# NodeSTM32.net
KiCad netlist of a schematic drawn in Altium Designer
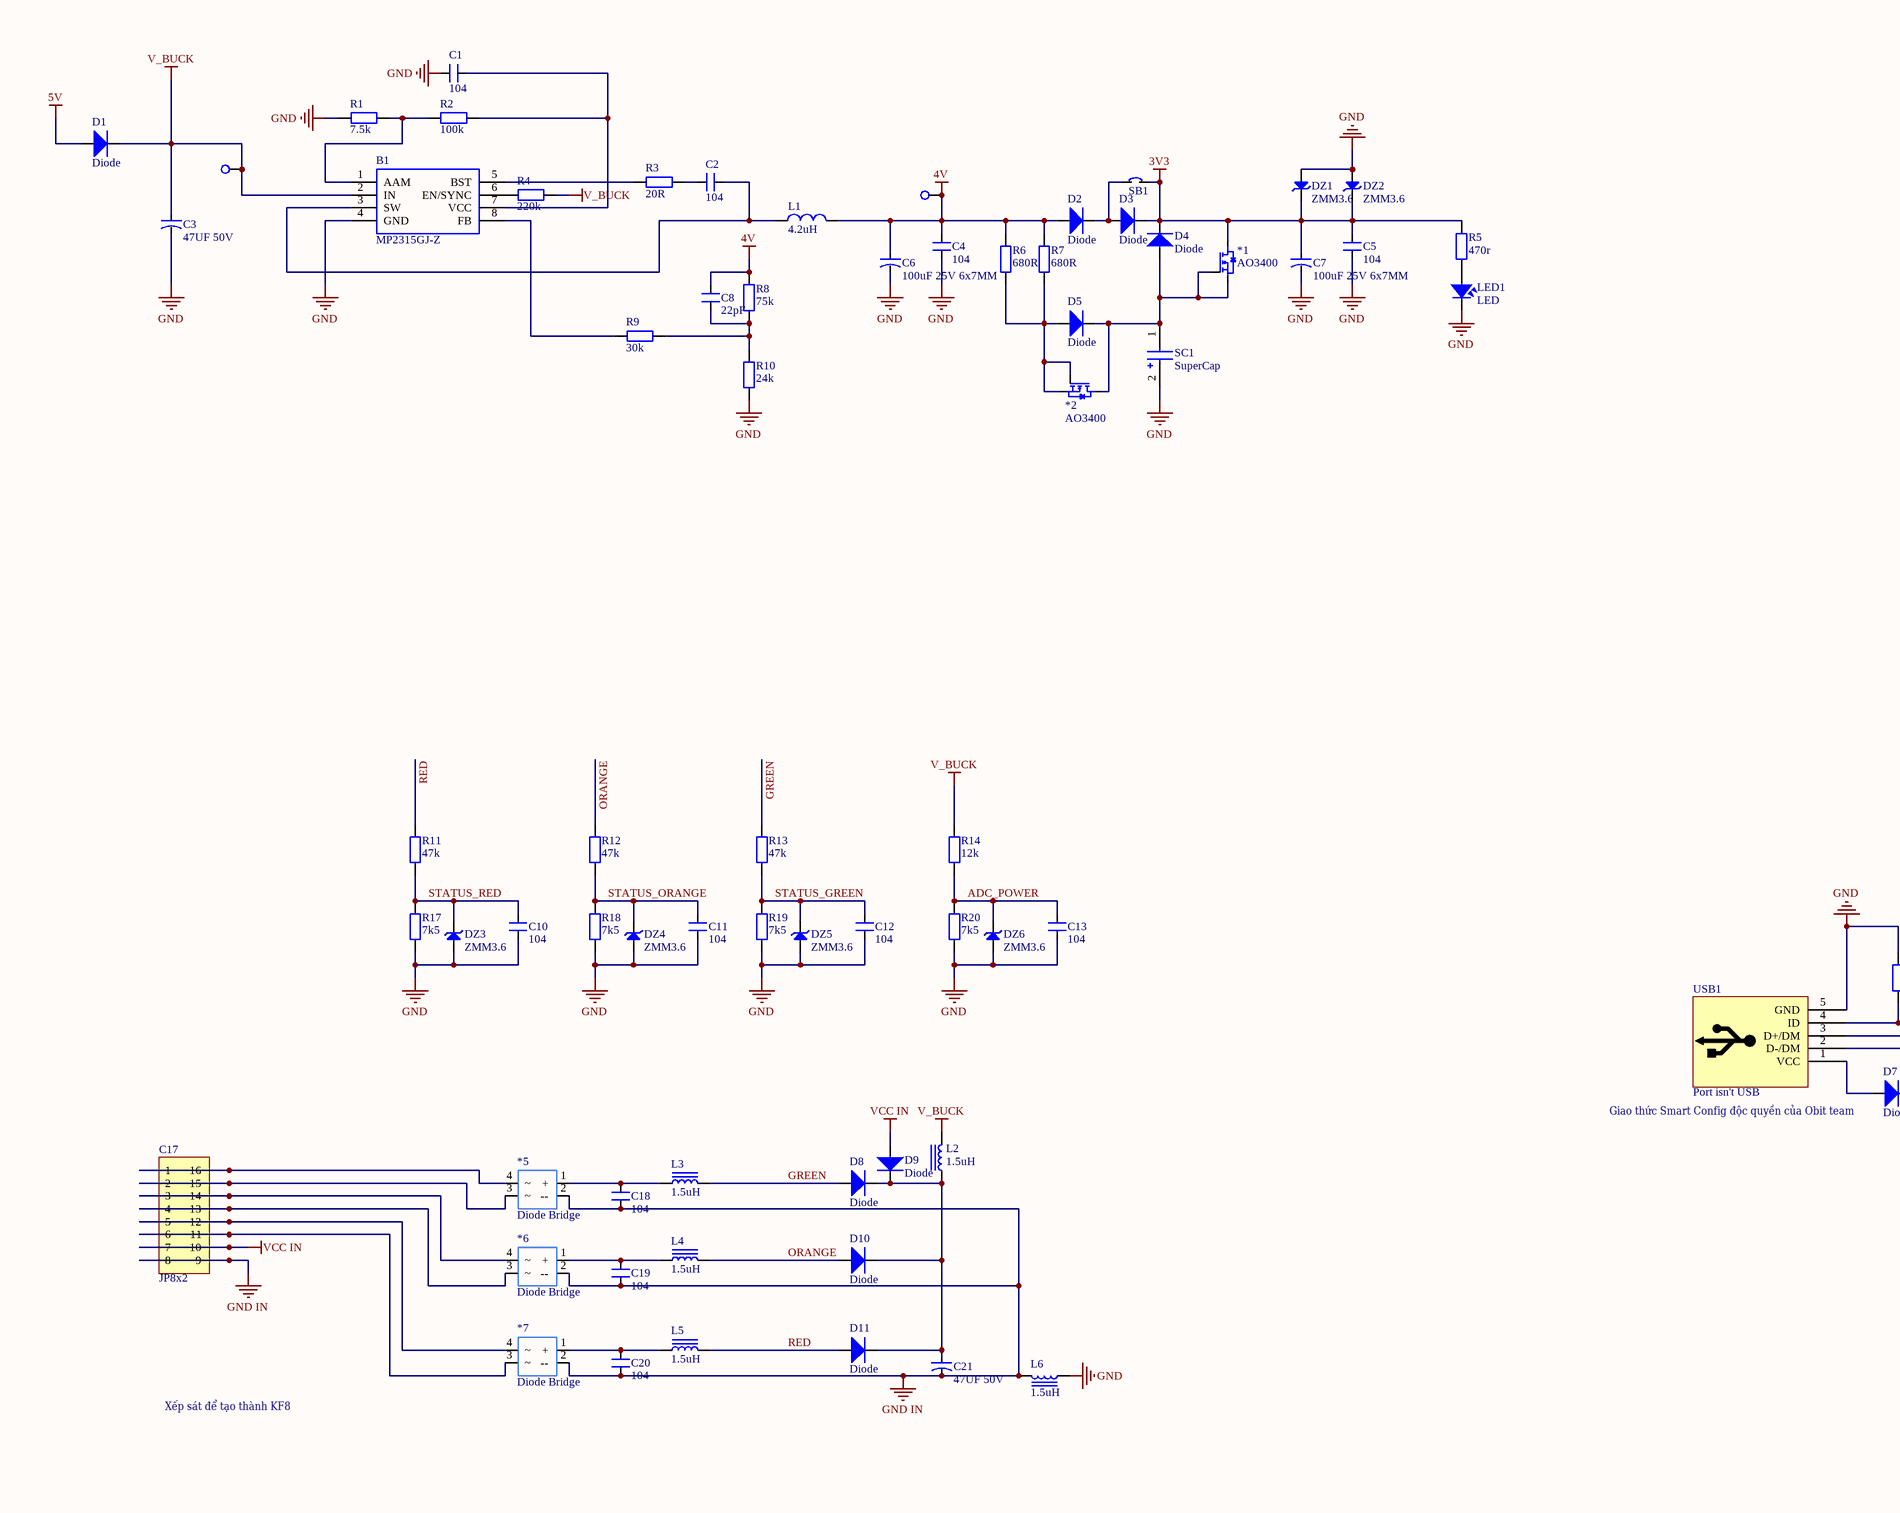
[diagram p0: NodeSTM32.SchDoc, left]
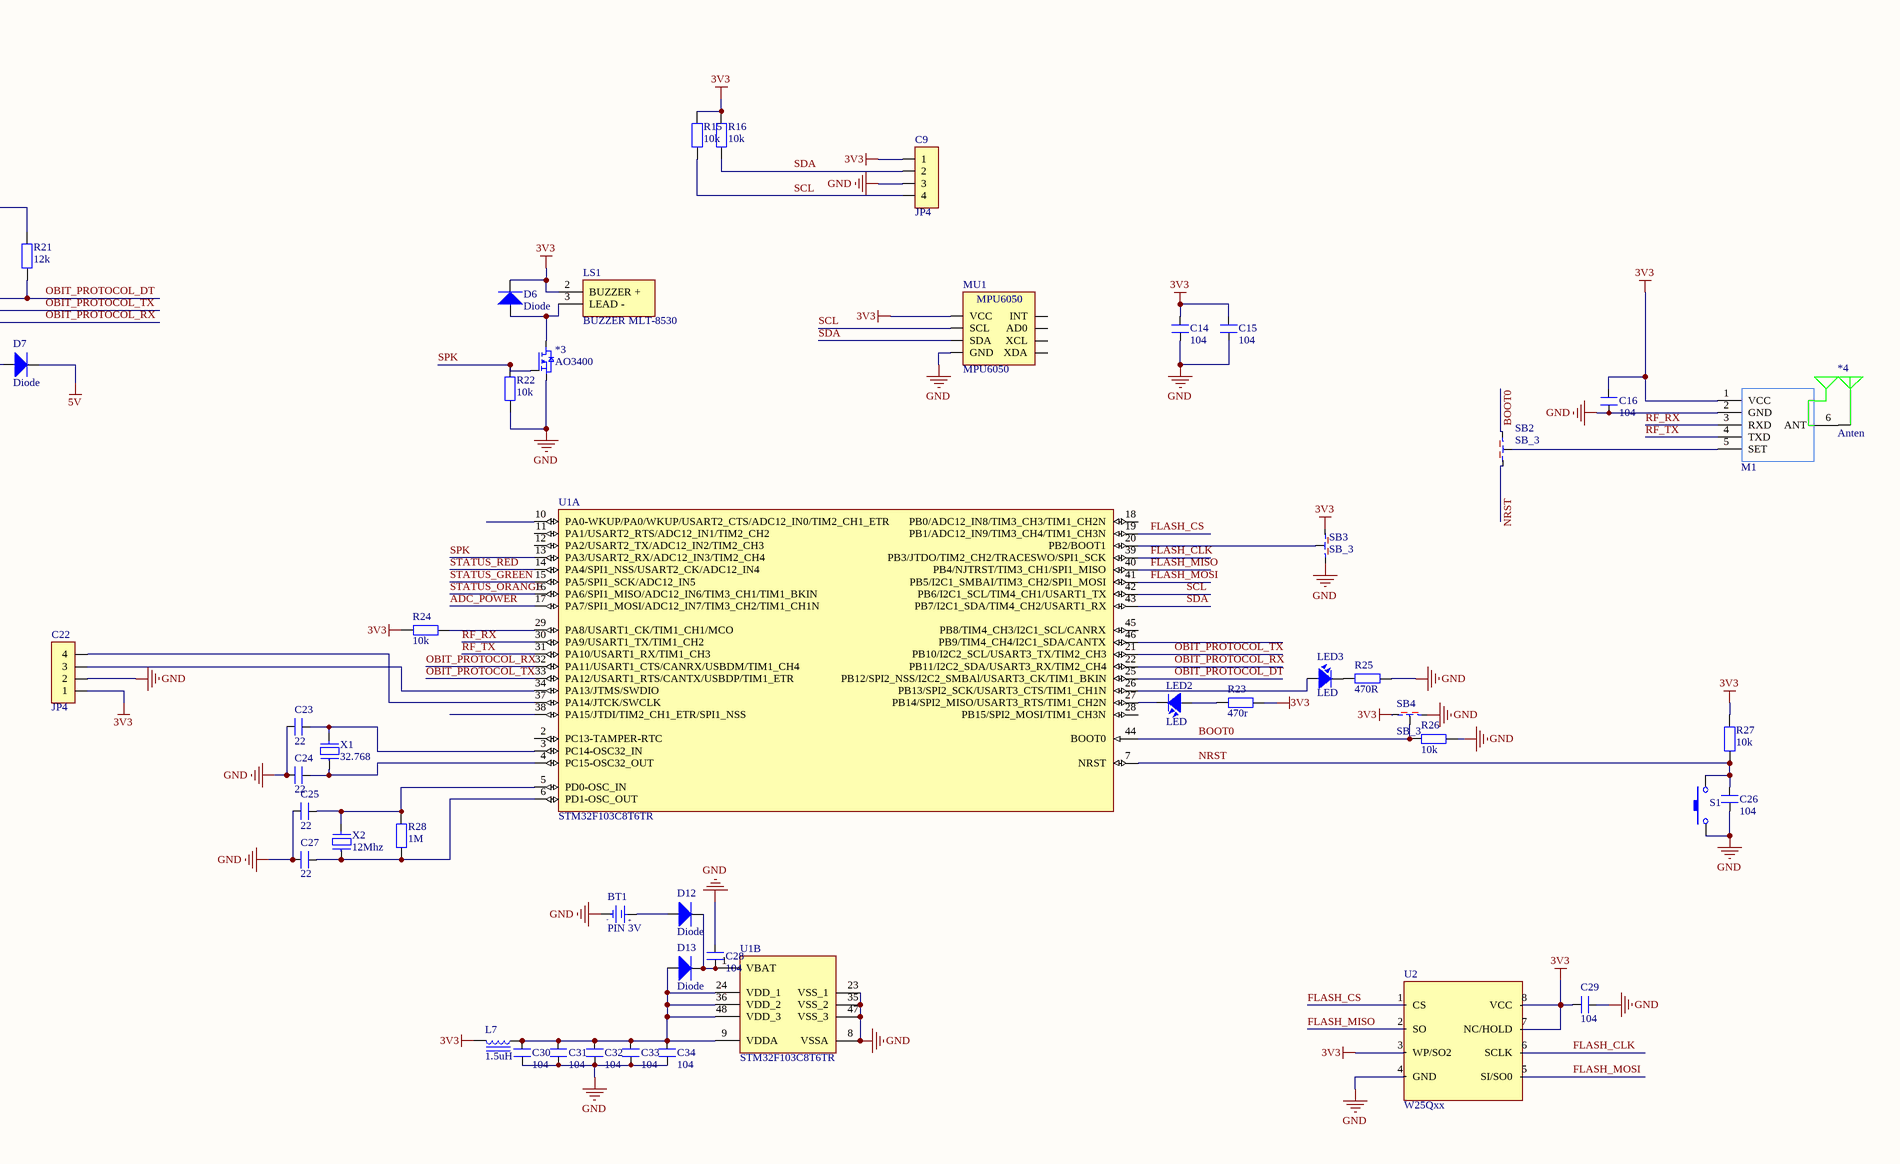
[diagram p1: NodeSTM32.SchDoc, right]

(export (version "E")
  (design (tool "Eeschema 10.0.6"))
  (components
    (comp (ref "*1") (value "AO3400") (footprint "SOT23-123") (libsource (lib "OBIT_TESLA") (part "AO3400")))
    (comp (ref "*2") (value "AO3400") (footprint "SOT23-123") (libsource (lib "OBIT_TESLA") (part "AO3400")))
    (comp (ref "*3") (value "AO3400") (footprint "SOT23-123") (libsource (lib "OBIT_TESLA") (part "AO3400")))
    (comp (ref "*4")
      (value "Anten")
      (footprint "LOXO_433_NGANG")
      (libsource (lib "OBIT_TESLA") (part "Anten"))
    )
    (comp (ref "*5")
      (value "Diode Bridge")
      (footprint "Diode Bridge 1A")
      (libsource (lib "OBIT_TESLA") (part "Diode Bridge"))
    )
    (comp (ref "*6")
      (value "Diode Bridge")
      (footprint "Diode Bridge 1A")
      (libsource (lib "OBIT_TESLA") (part "Diode Bridge"))
    )
    (comp (ref "*7")
      (value "Diode Bridge")
      (footprint "Diode Bridge 1A")
      (libsource (lib "OBIT_TESLA") (part "Diode Bridge"))
    )
    (comp (ref "*TP1") (value "TP") (footprint "TP") (libsource (lib "OBIT_TESLA") (part "TP")))
    (comp (ref "*TP2") (value "TP") (footprint "TP") (libsource (lib "OBIT_TESLA") (part "TP")))
    (comp (ref "B1")
      (value "MP2315GJ-Z")
      (footprint "SOT65P280X100-8N")
      (description "Switching Voltage Regulators 3A 24V 500kHz Sync buck")
      (libsource (lib "OBIT_TESLA") (part "MP2315GJ-Z"))
    )
    (comp (ref "BT1")
      (value "PIN 3V")
      (footprint "PIN CR1220-SMD")
      (description "Battery 3VDC")
      (libsource (lib "OBIT_TESLA") (part "PIN 3V"))
    )
    (comp (ref "C1")
      (value "104")
      (footprint "SM-0805")
      (description "Cap SMD")
      (libsource (lib "OBIT_TESLA") (part "CM"))
    )
    (comp (ref "C2")
      (value "104")
      (footprint "SM-0805")
      (description "Cap SMD")
      (libsource (lib "OBIT_TESLA") (part "CM"))
    )
    (comp (ref "C3")
      (value "47UF 50V")
      (footprint "CAP-ALU-SMD-6.3x7.7x2.2")
      (description "Tụ Nhôm 47UF 50V 6.3x5.5MM")
      (libsource (lib "Tesla_Thinh") (part "CN-ALU-SMD"))
    )
    (comp (ref "C4")
      (value "104")
      (footprint "SM-0805")
      (description "Cap SMD")
      (libsource (lib "OBIT_TESLA") (part "CM"))
    )
    (comp (ref "C5")
      (value "104")
      (footprint "SM-0805")
      (description "Cap SMD")
      (libsource (lib "OBIT_TESLA") (part "CM"))
    )
    (comp (ref "C6")
      (value "100uF 25V 6x7MM")
      (footprint "CAP-ALU-SMD-6.3x7.7x2.2")
      (description "Polarized Capacitor (Axial)")
      (libsource (lib "Tesla_Thinh") (part "CN-ALU-SMD"))
    )
    (comp (ref "C7")
      (value "100uF 25V 6x7MM")
      (footprint "CAP-ALU-SMD-6.3x7.7x2.2")
      (description "Polarized Capacitor (Axial)")
      (libsource (lib "Tesla_Thinh") (part "CN-ALU-SMD"))
    )
    (comp (ref "C8")
      (value "22pF")
      (footprint "SM-0805")
      (description "Cap SMD")
      (libsource (lib "OBIT_TESLA") (part "CM"))
    )
    (comp (ref "C9")
      (value "JP4")
      (footprint "JP4-C1T")
      (description "WR-PHD 2.54 mm Angled Socket Header")
      (fields
        (field (name "MANUFACTURER") "Würth Elektronik eiSos GmbH")
        (field (name "PARTNO") "613004143121")
      )
      (libsource (lib "OBIT_TESLA") (part "JP4"))
    )
    (comp (ref "C10")
      (value "104")
      (footprint "SM-0805")
      (description "Cap SMD")
      (libsource (lib "OBIT_TESLA") (part "CM"))
    )
    (comp (ref "C11")
      (value "104")
      (footprint "SM-0805")
      (description "Cap SMD")
      (libsource (lib "OBIT_TESLA") (part "CM"))
    )
    (comp (ref "C12")
      (value "104")
      (footprint "SM-0805")
      (description "Cap SMD")
      (libsource (lib "OBIT_TESLA") (part "CM"))
    )
    (comp (ref "C13")
      (value "104")
      (footprint "SM-0805")
      (description "Cap SMD")
      (libsource (lib "OBIT_TESLA") (part "CM"))
    )
    (comp (ref "C14")
      (value "104")
      (footprint "SM-0805")
      (description "Cap SMD")
      (libsource (lib "OBIT_TESLA") (part "CM"))
    )
    (comp (ref "C15")
      (value "104")
      (footprint "SM-0805")
      (description "Cap SMD")
      (libsource (lib "OBIT_TESLA") (part "CM"))
    )
    (comp (ref "C16")
      (value "104")
      (footprint "SM-0805")
      (description "Cap SMD")
      (libsource (lib "OBIT_TESLA") (part "CM"))
    )
    (comp (ref "C17")
      (value "JP8x2")
      (footprint "JP8-D2T")
      (description "WR-PHD 2.54 mm Dual Socket Header")
      (fields
        (field (name "MANUFACTURER") "Würth Elektronik eiSos GmbH")
        (field (name "PARTNO") "61301621821")
      )
      (libsource (lib "OBIT_TESLA") (part "JP8x2"))
    )
    (comp (ref "C18")
      (value "104")
      (footprint "SM-0805")
      (description "Cap SMD")
      (libsource (lib "OBIT_TESLA") (part "CM"))
    )
    (comp (ref "C19")
      (value "104")
      (footprint "SM-0805")
      (description "Cap SMD")
      (libsource (lib "OBIT_TESLA") (part "CM"))
    )
    (comp (ref "C20")
      (value "104")
      (footprint "SM-0805")
      (description "Cap SMD")
      (libsource (lib "OBIT_TESLA") (part "CM"))
    )
    (comp (ref "C21")
      (value "47UF 50V")
      (footprint "CAP-ALU-SMD-6.3x7.7x2.2")
      (description "Tụ Nhôm 47UF 50V 6.3x5.5MM")
      (libsource (lib "Tesla_Thinh") (part "CN-ALU-SMD"))
    )
    (comp (ref "C22")
      (value "JP4")
      (footprint "JP4-C1T")
      (description "WR-PHD 2.54 mm Angled Socket Header")
      (fields
        (field (name "MANUFACTURER") "Würth Elektronik eiSos GmbH")
        (field (name "PARTNO") "613004143121")
      )
      (libsource (lib "") (part "JP4_1"))
    )
    (comp (ref "C23")
      (value "22")
      (footprint "SM-0805")
      (description "Cap SMD")
      (libsource (lib "OBIT_TESLA") (part "CM"))
    )
    (comp (ref "C24")
      (value "22")
      (footprint "SM-0805")
      (description "Cap SMD")
      (libsource (lib "OBIT_TESLA") (part "CM"))
    )
    (comp (ref "C25")
      (value "22")
      (footprint "SM-0805")
      (description "Cap SMD")
      (libsource (lib "OBIT_TESLA") (part "CM"))
    )
    (comp (ref "C26")
      (value "104")
      (footprint "SM-0805")
      (description "Cap SMD")
      (libsource (lib "OBIT_TESLA") (part "CM"))
    )
    (comp (ref "C27")
      (value "22")
      (footprint "SM-0805")
      (description "Cap SMD")
      (libsource (lib "OBIT_TESLA") (part "CM"))
    )
    (comp (ref "C28")
      (value "104")
      (footprint "SM-0805")
      (description "Cap SMD")
      (libsource (lib "OBIT_TESLA") (part "CM"))
    )
    (comp (ref "C29")
      (value "104")
      (footprint "SM-0805")
      (description "Cap SMD")
      (libsource (lib "OBIT_TESLA") (part "CM"))
    )
    (comp (ref "C30")
      (value "104")
      (footprint "SM-0805")
      (description "Cap SMD")
      (libsource (lib "OBIT_TESLA") (part "CM"))
    )
    (comp (ref "C31")
      (value "104")
      (footprint "SM-0805")
      (description "Cap SMD")
      (libsource (lib "OBIT_TESLA") (part "CM"))
    )
    (comp (ref "C32")
      (value "104")
      (footprint "SM-0805")
      (description "Cap SMD")
      (libsource (lib "OBIT_TESLA") (part "CM"))
    )
    (comp (ref "C33")
      (value "104")
      (footprint "SM-0805")
      (description "Cap SMD")
      (libsource (lib "OBIT_TESLA") (part "CM"))
    )
    (comp (ref "C34")
      (value "104")
      (footprint "SM-0805")
      (description "Cap SMD")
      (libsource (lib "OBIT_TESLA") (part "CM"))
    )
    (comp (ref "D1") (value "Diode") (footprint "SOD123") (libsource (lib "OBIT_TESLA") (part "Diode")))
    (comp (ref "D2") (value "Diode") (footprint "DIO-SMD-123") (libsource (lib "OBIT_TESLA") (part "Diode")))
    (comp (ref "D3") (value "Diode") (footprint "DIO-SMD-123") (libsource (lib "OBIT_TESLA") (part "Diode")))
    (comp (ref "D4") (value "Diode") (footprint "DIO-SMD-123") (libsource (lib "OBIT_TESLA") (part "Diode")))
    (comp (ref "D5") (value "Diode") (footprint "DIO-SMD-123") (libsource (lib "OBIT_TESLA") (part "Diode")))
    (comp (ref "D6") (value "Diode") (footprint "DIO-SMD-123") (libsource (lib "OBIT_TESLA") (part "Diode")))
    (comp (ref "D7") (value "Diode") (footprint "DIO-SMD-123") (libsource (lib "OBIT_TESLA") (part "Diode")))
    (comp (ref "D8") (value "Diode") (footprint "DIO-SMD-123") (libsource (lib "OBIT_TESLA") (part "Diode")))
    (comp (ref "D9") (value "Diode") (footprint "DIO-SMD-123") (libsource (lib "OBIT_TESLA") (part "Diode")))
    (comp (ref "D10") (value "Diode") (footprint "DIO-SMD-123") (libsource (lib "OBIT_TESLA") (part "Diode")))
    (comp (ref "D11") (value "Diode") (footprint "DIO-SMD-123") (libsource (lib "OBIT_TESLA") (part "Diode")))
    (comp (ref "D12") (value "Diode") (footprint "SOD123") (libsource (lib "OBIT_TESLA") (part "Diode")))
    (comp (ref "D13") (value "Diode") (footprint "SOD123") (libsource (lib "OBIT_TESLA") (part "Diode")))
    (comp (ref "DZ1")
      (value "ZMM3.6")
      (footprint "SOD123")
      (description "DIODE GEN PURP 75V 200MA LLDS")
      (libsource (lib "Library") (part "DIODE Zener"))
    )
    (comp (ref "DZ2")
      (value "ZMM3.6")
      (footprint "DIO-SMD-123")
      (description "DIODE GEN PURP 75V 200MA LLDS")
      (libsource (lib "Library") (part "DIODE Zener"))
    )
    (comp (ref "DZ3")
      (value "ZMM3.6")
      (footprint "SOD123")
      (description "DIODE GEN PURP 75V 200MA LLDS")
      (libsource (lib "Library") (part "DIODE Zener"))
    )
    (comp (ref "DZ4")
      (value "ZMM3.6")
      (footprint "SOD123")
      (description "DIODE GEN PURP 75V 200MA LLDS")
      (libsource (lib "Library") (part "DIODE Zener"))
    )
    (comp (ref "DZ5")
      (value "ZMM3.6")
      (footprint "SOD123")
      (description "DIODE GEN PURP 75V 200MA LLDS")
      (libsource (lib "Library") (part "DIODE Zener"))
    )
    (comp (ref "DZ6")
      (value "ZMM3.6")
      (footprint "SOD123")
      (description "DIODE GEN PURP 75V 200MA LLDS")
      (libsource (lib "Library") (part "DIODE Zener"))
    )
    (comp (ref "L1")
      (value "4.2uH")
      (footprint "IND 4532-2P")
      (libsource (lib "AltiumLibraryTieuBao (1)") (part "INDUCTOR B"))
    )
    (comp (ref "L2")
      (value "1.5uH")
      (footprint "FER 0805/2012")
      (description "SMT Inductor")
      (libsource (lib "OBIT_TESLA") (part "Inductor"))
    )
    (comp (ref "L3")
      (value "1.5uH")
      (footprint "FER 0805/2012")
      (description "SMT Inductor")
      (libsource (lib "OBIT_TESLA") (part "Inductor"))
    )
    (comp (ref "L4")
      (value "1.5uH")
      (footprint "FER 0805/2012")
      (description "SMT Inductor")
      (libsource (lib "OBIT_TESLA") (part "Inductor"))
    )
    (comp (ref "L5")
      (value "1.5uH")
      (footprint "FER 0805/2012")
      (description "SMT Inductor")
      (libsource (lib "OBIT_TESLA") (part "Inductor"))
    )
    (comp (ref "L6")
      (value "1.5uH")
      (footprint "FER 0805/2012")
      (description "SMT Inductor")
      (libsource (lib "OBIT_TESLA") (part "Inductor"))
    )
    (comp (ref "L7")
      (value "1.5uH")
      (footprint "FER 0805/2012")
      (description "SMT Inductor")
      (libsource (lib "OBIT_TESLA") (part "Inductor"))
    )
    (comp (ref "LED1")
      (value "LED")
      (footprint "SM-LED-0805-Blue")
      (libsource (lib "OBIT_TESLA") (part "LED"))
    )
    (comp (ref "LED2")
      (value "LED")
      (footprint "SM-LED-0805-Blue")
      (libsource (lib "OBIT_TESLA") (part "LED"))
    )
    (comp (ref "LED3")
      (value "LED")
      (footprint "SM-LED-0805-Blue")
      (libsource (lib "OBIT_TESLA") (part "LED"))
    )
    (comp (ref "LS1")
      (value "BUZZER MLT-8530")
      (footprint "MLT8530")
      (description "Loudspeaker or Buzzer")
      (fields (field (name "MANUFACTURER_PART_NUMBER") "MLT-8530"))
      (libsource (lib "OBIT_TESLA") (part "BUZZER MLT-8530"))
    )
    (comp (ref "M1")
      (value "CC1101")
      (footprint "CC1101 UART HC11")
      (description "OBIT TEAM\r\nCC1101 UART 433MHZ")
      (libsource (lib "OBIT_TESLA") (part "CC1101 UART HC11"))
    )
    (comp (ref "MU1")
      (value "MPU6050")
      (footprint "MPU6050")
      (fields
        (field (name "MANUFACTURER") "Würth Elektronik eiSos GmbH")
        (field (name "PARTNO") "613004143121")
      )
      (libsource (lib "Tesla_Thinh") (part "MPU6050"))
    )
    (comp (ref "R1")
      (value "7.5k")
      (footprint "RES-SMD-0805")
      (description "Resistor R1/4W")
      (libsource (lib "OBIT_TESLA") (part "R"))
    )
    (comp (ref "R2")
      (value "100k")
      (footprint "RES-SMD-0805")
      (description "Resistor R1/4W")
      (libsource (lib "OBIT_TESLA") (part "R"))
    )
    (comp (ref "R3")
      (value "20R")
      (footprint "RES-SMD-0805")
      (description "Resistor R1/4W")
      (libsource (lib "OBIT_TESLA") (part "R"))
    )
    (comp (ref "R4")
      (value "220k")
      (footprint "RES-SMD-0805")
      (description "Resistor R1/4W")
      (libsource (lib "OBIT_TESLA") (part "R"))
    )
    (comp (ref "R5")
      (value "470r")
      (footprint "RES-SMD-0805")
      (description "Resistor R1/4W")
      (libsource (lib "OBIT_TESLA") (part "R"))
    )
    (comp (ref "R6")
      (value "680R")
      (footprint "RES-SMD-0805")
      (description "Resistor R1/4W")
      (libsource (lib "OBIT_TESLA") (part "R"))
    )
    (comp (ref "R7")
      (value "680R")
      (footprint "RES-SMD-0805")
      (description "Resistor R1/4W")
      (libsource (lib "OBIT_TESLA") (part "R"))
    )
    (comp (ref "R8")
      (value "75k")
      (footprint "RES-SMD-0805")
      (description "Resistor R1/4W")
      (libsource (lib "OBIT_TESLA") (part "R"))
    )
    (comp (ref "R9")
      (value "30k")
      (footprint "RES-SMD-0805")
      (description "Resistor R1/4W")
      (libsource (lib "OBIT_TESLA") (part "R"))
    )
    (comp (ref "R10")
      (value "24k")
      (footprint "RES-SMD-0805")
      (description "Resistor R1/4W")
      (libsource (lib "OBIT_TESLA") (part "R"))
    )
    (comp (ref "R11")
      (value "47k")
      (footprint "RES-SMD-0805")
      (description "Resistor R1/4W")
      (libsource (lib "OBIT_TESLA") (part "R"))
    )
    (comp (ref "R12")
      (value "47k")
      (footprint "RES-SMD-0805")
      (description "Resistor R1/4W")
      (libsource (lib "OBIT_TESLA") (part "R"))
    )
    (comp (ref "R13")
      (value "47k")
      (footprint "RES-SMD-0805")
      (description "Resistor R1/4W")
      (libsource (lib "OBIT_TESLA") (part "R"))
    )
    (comp (ref "R14")
      (value "12k")
      (footprint "RES-SMD-0805")
      (description "Resistor R1/4W")
      (libsource (lib "OBIT_TESLA") (part "R"))
    )
    (comp (ref "R15")
      (value "10k")
      (footprint "RES-SMD-0805")
      (description "Resistor R1/4W")
      (libsource (lib "OBIT_TESLA") (part "R"))
    )
    (comp (ref "R16")
      (value "10k")
      (footprint "RES-SMD-0805")
      (description "Resistor R1/4W")
      (libsource (lib "OBIT_TESLA") (part "R"))
    )
    (comp (ref "R17")
      (value "7k5")
      (footprint "RES-SMD-0805")
      (description "Resistor R1/4W")
      (libsource (lib "OBIT_TESLA") (part "R"))
    )
    (comp (ref "R18")
      (value "7k5")
      (footprint "RES-SMD-0805")
      (description "Resistor R1/4W")
      (libsource (lib "OBIT_TESLA") (part "R"))
    )
    (comp (ref "R19")
      (value "7k5")
      (footprint "RES-SMD-0805")
      (description "Resistor R1/4W")
      (libsource (lib "OBIT_TESLA") (part "R"))
    )
    (comp (ref "R20")
      (value "7k5")
      (footprint "RES-SMD-0805")
      (description "Resistor R1/4W")
      (libsource (lib "OBIT_TESLA") (part "R"))
    )
    (comp (ref "R21")
      (value "12k")
      (footprint "RES-SMD-0805")
      (description "Resistor R1/4W")
      (libsource (lib "OBIT_TESLA") (part "R"))
    )
    (comp (ref "R22")
      (value "10k")
      (footprint "RES-SMD-0805")
      (description "Resistor R1/4W")
      (libsource (lib "OBIT_TESLA") (part "R"))
    )
    (comp (ref "R23")
      (value "470r")
      (footprint "RES-SMD-0805")
      (description "Resistor R1/4W")
      (libsource (lib "OBIT_TESLA") (part "R"))
    )
    (comp (ref "R24")
      (value "10k")
      (footprint "RES-SMD-0805")
      (description "Resistor R1/4W")
      (libsource (lib "OBIT_TESLA") (part "R"))
    )
    (comp (ref "R25")
      (value "470R")
      (footprint "RES-SMD-0805")
      (description "Resistor R1/4W")
      (libsource (lib "OBIT_TESLA") (part "R"))
    )
    (comp (ref "R26")
      (value "10k")
      (footprint "RES-SMD-0805")
      (description "Resistor R1/4W")
      (libsource (lib "OBIT_TESLA") (part "R"))
    )
    (comp (ref "R27")
      (value "10k")
      (footprint "RES-SMD-0805")
      (description "Resistor R1/4W")
      (libsource (lib "OBIT_TESLA") (part "R"))
    )
    (comp (ref "R28")
      (value "1M")
      (footprint "RES-SMD-0805")
      (description "Resistor R1/4W")
      (libsource (lib "OBIT_TESLA") (part "R"))
    )
    (comp (ref "S1")
      (value "SW")
      (footprint "BUTTON-SMD 2PIN")
      (description "Switch-Button")
      (libsource (lib "OBIT_TESLA") (part "SW-Button"))
    )
    (comp (ref "SB1") (value "SB") (footprint "SB") (libsource (lib "OBIT_TESLA") (part "SB")))
    (comp (ref "SB2") (value "SB_3") (footprint "SB_3") (libsource (lib "OBIT_TESLA") (part "SB_3")))
    (comp (ref "SB3") (value "SB_3") (footprint "SB_3") (libsource (lib "OBIT_TESLA") (part "SB_3")))
    (comp (ref "SB4") (value "SB_3") (footprint "SB_3") (libsource (lib "OBIT_TESLA") (part "SB_3")))
    (comp (ref "SC1")
      (value "SuperCap")
      (footprint "SuperCapacitor")
      (libsource (lib "OBIT_TESLA") (part "5.5V 0.22F"))
    )
    (comp (ref "U1")
      (value "STM32F103C8T6TR")
      (footprint "STM-LQFP48_N")
      (libsource (lib "OBIT_TESLA") (part "STM32F103C8T6TR"))
    )
    (comp (ref "U2") (value "W25Qxx") (footprint "SO-8N") (libsource (lib "OBIT_TESLA") (part "W25Qxx")))
    (comp (ref "USB1")
      (value "Port isn't USB")
      (footprint "USB-M1")
      (libsource (lib "OBIT_TESLA") (part "USB_M"))
    )
    (comp (ref "X1")
      (value "32.768")
      (footprint "XT32k")
      (description "Crystal, 32.768 KHz, -40 to 85 degC, 3.2 x 1.5 x 0.9 mm SMD")
      (libsource (lib "OBIT_TESLA") (part "XT2"))
    )
    (comp (ref "X2")
      (value "12Mhz")
      (footprint "XT2")
      (description "Crystal, 32.768 KHz, -40 to 85 degC, 3.2 x 1.5 x 0.9 mm SMD")
      (libsource (lib "OBIT_TESLA") (part "XT2"))
    )
  )
  (nets
    (net (code "1") (name "/ADC_POWER") (class "Default")
      (node (ref "C13") (pin "2") (pinfunction "2_2") (pintype "passive"))
      (node (ref "DZ6") (pin "2") (pinfunction "K_2") (pintype "passive"))
      (node (ref "R14") (pin "2") (pinfunction "2_2") (pintype "passive"))
      (node (ref "R20") (pin "1") (pinfunction "1_1") (pintype "passive"))
      (node (ref "U1") (pin "17") (pinfunction "PA7/SPI1_MOSI/ADC12_IN7/TIM3_CH2/TIM1_CH1N_17") (pintype "bidirectional"))
    )
    (net (code "2") (name "/BOOT0") (class "Default")
      (node (ref "R26") (pin "2") (pinfunction "2_2") (pintype "passive"))
      (node (ref "SB2") (pin "3") (pinfunction "3_3") (pintype "passive"))
      (node (ref "SB4") (pin "2") (pinfunction "2_2") (pintype "passive"))
      (node (ref "U1") (pin "44") (pinfunction "BOOT0_44") (pintype "input"))
    )
    (net (code "3") (name "/FLASH_CLK") (class "Default")
      (node (ref "U1") (pin "39") (pinfunction "PB3/JTDO/TIM2_CH2/TRACESWO/SPI1_SCK_39") (pintype "bidirectional"))
      (node (ref "U2") (pin "6") (pinfunction "SCLK_6") (pintype "passive"))
    )
    (net (code "4") (name "/FLASH_CS") (class "Default")
      (node (ref "U1") (pin "19") (pinfunction "PB1/ADC12_IN9/TIM3_CH4/TIM1_CH3N_19") (pintype "bidirectional"))
      (node (ref "U2") (pin "1") (pinfunction "CS_1") (pintype "passive"))
    )
    (net (code "5") (name "/FLASH_MISO") (class "Default")
      (node (ref "U1") (pin "40") (pinfunction "PB4/NJTRST/TIM3_CH1/SPI1_MISO_40") (pintype "bidirectional"))
      (node (ref "U2") (pin "2") (pinfunction "SO_2") (pintype "passive"))
    )
    (net (code "6") (name "/FLASH_MOSI") (class "Default")
      (node (ref "U1") (pin "41") (pinfunction "PB5/I2C1_SMBAI/TIM3_CH2/SPI1_MOSI_41") (pintype "bidirectional"))
      (node (ref "U2") (pin "5") (pinfunction "SI/SO0_5") (pintype "passive"))
    )
    (net (code "7") (name "/GREEN") (class "Default")
      (node (ref "D8") (pin "1") (pinfunction "1_1") (pintype "passive"))
      (node (ref "L3") (pin "2") (pinfunction "2_2") (pintype "passive"))
      (node (ref "R13") (pin "1") (pinfunction "1_1") (pintype "passive"))
    )
    (net (code "8") (name "/NRST") (class "Default")
      (node (ref "C26") (pin "1") (pinfunction "1_1") (pintype "passive"))
      (node (ref "R27") (pin "1") (pinfunction "1_1") (pintype "passive"))
      (node (ref "S1") (pin "2") (pinfunction "2_2") (pintype "passive"))
      (node (ref "SB2") (pin "1") (pinfunction "1_1") (pintype "passive"))
      (node (ref "U1") (pin "7") (pinfunction "NRST_7") (pintype "bidirectional"))
    )
    (net (code "9") (name "/OBIT_PROTOCOL_DT") (class "Default")
      (node (ref "R21") (pin "2") (pinfunction "2_2") (pintype "passive"))
      (node (ref "U1") (pin "25") (pinfunction "PB12/SPI2_NSS/I2C2_SMBAl/USART3_CK/TIM1_BKIN_25") (pintype "bidirectional"))
      (node (ref "USB1") (pin "4") (pinfunction "ID_4") (pintype "passive"))
    )
    (net (code "10") (name "/OBIT_PROTOCOL_RX") (class "Default")
      (node (ref "U1") (pin "22") (pinfunction "PB11/I2C2_SDA/USART3_RX/TIM2_CH4_22") (pintype "bidirectional"))
      (node (ref "U1") (pin "32") (pinfunction "PA11/USART1_CTS/CANRX/USBDM/TIM1_CH4_32") (pintype "bidirectional"))
      (node (ref "USB1") (pin "2") (pinfunction "D-/DM_2") (pintype "passive"))
    )
    (net (code "11") (name "/OBIT_PROTOCOL_TX") (class "Default")
      (node (ref "U1") (pin "21") (pinfunction "PB10/I2C2_SCL/USART3_TX/TIM2_CH3_21") (pintype "bidirectional"))
      (node (ref "U1") (pin "33") (pinfunction "PA12/USART1_RTS/CANTX/USBDP/TIM1_ETR_33") (pintype "bidirectional"))
      (node (ref "USB1") (pin "3") (pinfunction "D+/DM_3") (pintype "passive"))
    )
    (net (code "12") (name "/ORANGE") (class "Default")
      (node (ref "D10") (pin "1") (pinfunction "1_1") (pintype "passive"))
      (node (ref "L4") (pin "2") (pinfunction "2_2") (pintype "passive"))
      (node (ref "R12") (pin "1") (pinfunction "1_1") (pintype "passive"))
    )
    (net (code "13") (name "/RED") (class "Default")
      (node (ref "D11") (pin "1") (pinfunction "1_1") (pintype "passive"))
      (node (ref "L5") (pin "2") (pinfunction "2_2") (pintype "passive"))
      (node (ref "R11") (pin "1") (pinfunction "1_1") (pintype "passive"))
    )
    (net (code "14") (name "/RF_RX") (class "Default")
      (node (ref "M1") (pin "3") (pinfunction "RXD_3") (pintype "passive"))
      (node (ref "U1") (pin "30") (pinfunction "PA9/USART1_TX/TIM1_CH2_30") (pintype "bidirectional"))
    )
    (net (code "15") (name "/RF_TX") (class "Default")
      (node (ref "M1") (pin "4") (pinfunction "TXD_4") (pintype "passive"))
      (node (ref "U1") (pin "31") (pinfunction "PA10/USART1_RX/TIM1_CH3_31") (pintype "bidirectional"))
    )
    (net (code "16") (name "/SCL") (class "Default")
      (node (ref "C9") (pin "4") (pinfunction "4_4") (pintype "passive"))
      (node (ref "MU1") (pin "3") (pinfunction "SCL_3") (pintype "passive"))
      (node (ref "R15") (pin "1") (pinfunction "1_1") (pintype "passive"))
      (node (ref "U1") (pin "42") (pinfunction "PB6/I2C1_SCL/TIM4_CH1/USART1_TX_42") (pintype "bidirectional"))
    )
    (net (code "17") (name "/SDA") (class "Default")
      (node (ref "C9") (pin "2") (pinfunction "2_2") (pintype "passive"))
      (node (ref "MU1") (pin "4") (pinfunction "SDA_4") (pintype "passive"))
      (node (ref "R16") (pin "1") (pinfunction "1_1") (pintype "passive"))
      (node (ref "U1") (pin "43") (pinfunction "PB7/I2C1_SDA/TIM4_CH2/USART1_RX_43") (pintype "bidirectional"))
    )
    (net (code "18") (name "/SPK") (class "Default")
      (node (ref "*3") (pin "1") (pintype "passive"))
      (node (ref "R22") (pin "1") (pinfunction "1_1") (pintype "passive"))
      (node (ref "U1") (pin "13") (pinfunction "PA3/USART2_RX/ADC12_IN3/TIM2_CH4_13") (pintype "bidirectional"))
    )
    (net (code "19") (name "/STATUS_GREEN") (class "Default")
      (node (ref "C12") (pin "2") (pinfunction "2_2") (pintype "passive"))
      (node (ref "DZ5") (pin "2") (pinfunction "K_2") (pintype "passive"))
      (node (ref "R13") (pin "2") (pinfunction "2_2") (pintype "passive"))
      (node (ref "R19") (pin "1") (pinfunction "1_1") (pintype "passive"))
      (node (ref "U1") (pin "15") (pinfunction "PA5/SPI1_SCK/ADC12_IN5_15") (pintype "bidirectional"))
    )
    (net (code "20") (name "/STATUS_ORANGE") (class "Default")
      (node (ref "C11") (pin "2") (pinfunction "2_2") (pintype "passive"))
      (node (ref "DZ4") (pin "2") (pinfunction "K_2") (pintype "passive"))
      (node (ref "R12") (pin "2") (pinfunction "2_2") (pintype "passive"))
      (node (ref "R18") (pin "1") (pinfunction "1_1") (pintype "passive"))
      (node (ref "U1") (pin "16") (pinfunction "PA6/SPI1_MISO/ADC12_IN6/TIM3_CH1/TIM1_BKIN_16") (pintype "bidirectional"))
    )
    (net (code "21") (name "/STATUS_RED") (class "Default")
      (node (ref "C10") (pin "2") (pinfunction "2_2") (pintype "passive"))
      (node (ref "DZ3") (pin "2") (pinfunction "K_2") (pintype "passive"))
      (node (ref "R11") (pin "2") (pinfunction "2_2") (pintype "passive"))
      (node (ref "R17") (pin "1") (pinfunction "1_1") (pintype "passive"))
      (node (ref "U1") (pin "14") (pinfunction "PA4/SPI1_NSS/USART2_CK/ADC12_IN4_14") (pintype "bidirectional"))
    )
    (net (code "22") (name "3V3") (class "Default")
      (node (ref "*1") (pin "2") (pintype "passive"))
      (node (ref "C14") (pin "2") (pinfunction "2_2") (pintype "passive"))
      (node (ref "C15") (pin "2") (pinfunction "2_2") (pintype "passive"))
      (node (ref "C16") (pin "2") (pinfunction "2_2") (pintype "passive"))
      (node (ref "C22") (pin "1") (pinfunction "1_1") (pintype "passive"))
      (node (ref "C29") (pin "1") (pinfunction "1_1") (pintype "passive"))
      (node (ref "C5") (pin "2") (pinfunction "2_2") (pintype "passive"))
      (node (ref "C7") (pin "1") (pinfunction "1_1") (pintype "passive"))
      (node (ref "C9") (pin "1") (pinfunction "1_1") (pintype "passive"))
      (node (ref "D3") (pin "2") (pinfunction "2_2") (pintype "passive"))
      (node (ref "D4") (pin "2") (pinfunction "2_2") (pintype "passive"))
      (node (ref "D6") (pin "2") (pinfunction "2_2") (pintype "passive"))
      (node (ref "DZ1") (pin "2") (pinfunction "K_2") (pintype "passive"))
      (node (ref "DZ2") (pin "2") (pinfunction "K_2") (pintype "passive"))
      (node (ref "L7") (pin "2") (pinfunction "2_2") (pintype "passive"))
      (node (ref "LS1") (pin "2") (pinfunction "BUZZER_+_2") (pintype "passive"))
      (node (ref "M1") (pin "1") (pinfunction "VCC_1") (pintype "passive"))
      (node (ref "MU1") (pin "1") (pinfunction "VCC_1") (pintype "passive"))
      (node (ref "R15") (pin "2") (pinfunction "2_2") (pintype "passive"))
      (node (ref "R16") (pin "2") (pinfunction "2_2") (pintype "passive"))
      (node (ref "R23") (pin "2") (pinfunction "2_2") (pintype "passive"))
      (node (ref "R24") (pin "2") (pinfunction "2_2") (pintype "passive"))
      (node (ref "R27") (pin "2") (pinfunction "2_2") (pintype "passive"))
      (node (ref "R5") (pin "2") (pinfunction "2_2") (pintype "passive"))
      (node (ref "SB1") (pin "2") (pintype "passive"))
      (node (ref "SB3") (pin "1") (pinfunction "1_1") (pintype "passive"))
      (node (ref "SB4") (pin "1") (pinfunction "1_1") (pintype "passive"))
      (node (ref "U2") (pin "3") (pinfunction "WP/SO2_3") (pintype "passive"))
      (node (ref "U2") (pin "7") (pinfunction "NC/HOLD_7") (pintype "passive"))
      (node (ref "U2") (pin "8") (pinfunction "VCC_8") (pintype "passive"))
    )
    (net (code "23") (name "4V") (class "Default")
      (node (ref "*TP2") (pin "1") (pintype "passive"))
      (node (ref "C4") (pin "2") (pinfunction "2_2") (pintype "passive"))
      (node (ref "C6") (pin "1") (pinfunction "1_1") (pintype "passive"))
      (node (ref "C8") (pin "2") (pinfunction "2_2") (pintype "passive"))
      (node (ref "D2") (pin "1") (pinfunction "1_1") (pintype "passive"))
      (node (ref "L1") (pin "2") (pinfunction "2_2") (pintype "passive"))
      (node (ref "R6") (pin "1") (pinfunction "1_1") (pintype "passive"))
      (node (ref "R7") (pin "1") (pinfunction "1_1") (pintype "passive"))
      (node (ref "R8") (pin "1") (pinfunction "1_1") (pintype "passive"))
    )
    (net (code "24") (name "5V") (class "Default")
      (node (ref "D1") (pin "1") (pinfunction "1_1") (pintype "passive"))
      (node (ref "D7") (pin "2") (pinfunction "2_2") (pintype "passive"))
    )
    (net (code "25") (name "GND") (class "Default")
      (node (ref "*3") (pin "3") (pintype "passive"))
      (node (ref "B1") (pin "4") (pinfunction "GND_4") (pintype "passive"))
      (node (ref "BT1") (pin "2") (pinfunction "GND_2") (pintype "passive"))
      (node (ref "C1") (pin "2") (pinfunction "2_2") (pintype "passive"))
      (node (ref "C10") (pin "1") (pinfunction "1_1") (pintype "passive"))
      (node (ref "C11") (pin "1") (pinfunction "1_1") (pintype "passive"))
      (node (ref "C12") (pin "1") (pinfunction "1_1") (pintype "passive"))
      (node (ref "C13") (pin "1") (pinfunction "1_1") (pintype "passive"))
      (node (ref "C14") (pin "1") (pinfunction "1_1") (pintype "passive"))
      (node (ref "C15") (pin "1") (pinfunction "1_1") (pintype "passive"))
      (node (ref "C16") (pin "1") (pinfunction "1_1") (pintype "passive"))
      (node (ref "C22") (pin "2") (pinfunction "2_2") (pintype "passive"))
      (node (ref "C23") (pin "2") (pinfunction "2_2") (pintype "passive"))
      (node (ref "C24") (pin "2") (pinfunction "2_2") (pintype "passive"))
      (node (ref "C25") (pin "2") (pinfunction "2_2") (pintype "passive"))
      (node (ref "C26") (pin "2") (pinfunction "2_2") (pintype "passive"))
      (node (ref "C27") (pin "2") (pinfunction "2_2") (pintype "passive"))
      (node (ref "C28") (pin "1") (pinfunction "1_1") (pintype "passive"))
      (node (ref "C29") (pin "2") (pinfunction "2_2") (pintype "passive"))
      (node (ref "C3") (pin "2") (pinfunction "2_2") (pintype "passive"))
      (node (ref "C30") (pin "2") (pinfunction "2_2") (pintype "passive"))
      (node (ref "C31") (pin "2") (pinfunction "2_2") (pintype "passive"))
      (node (ref "C32") (pin "2") (pinfunction "2_2") (pintype "passive"))
      (node (ref "C33") (pin "2") (pinfunction "2_2") (pintype "passive"))
      (node (ref "C34") (pin "2") (pinfunction "2_2") (pintype "passive"))
      (node (ref "C4") (pin "1") (pinfunction "1_1") (pintype "passive"))
      (node (ref "C5") (pin "1") (pinfunction "1_1") (pintype "passive"))
      (node (ref "C6") (pin "2") (pinfunction "2_2") (pintype "passive"))
      (node (ref "C7") (pin "2") (pinfunction "2_2") (pintype "passive"))
      (node (ref "C9") (pin "3") (pinfunction "3_3") (pintype "passive"))
      (node (ref "DZ1") (pin "1") (pinfunction "A_1") (pintype "passive"))
      (node (ref "DZ2") (pin "1") (pinfunction "A_1") (pintype "passive"))
      (node (ref "DZ3") (pin "1") (pinfunction "A_1") (pintype "passive"))
      (node (ref "DZ4") (pin "1") (pinfunction "A_1") (pintype "passive"))
      (node (ref "DZ5") (pin "1") (pinfunction "A_1") (pintype "passive"))
      (node (ref "DZ6") (pin "1") (pinfunction "A_1") (pintype "passive"))
      (node (ref "L6") (pin "1") (pinfunction "1_1") (pintype "passive"))
      (node (ref "LED1") (pin "2") (pinfunction "2_2") (pintype "passive"))
      (node (ref "M1") (pin "2") (pinfunction "GND_2") (pintype "passive"))
      (node (ref "MU1") (pin "2") (pinfunction "GND_2") (pintype "passive"))
      (node (ref "R1") (pin "2") (pinfunction "2_2") (pintype "passive"))
      (node (ref "R10") (pin "2") (pinfunction "2_2") (pintype "passive"))
      (node (ref "R17") (pin "2") (pinfunction "2_2") (pintype "passive"))
      (node (ref "R18") (pin "2") (pinfunction "2_2") (pintype "passive"))
      (node (ref "R19") (pin "2") (pinfunction "2_2") (pintype "passive"))
      (node (ref "R20") (pin "2") (pinfunction "2_2") (pintype "passive"))
      (node (ref "R21") (pin "1") (pinfunction "1_1") (pintype "passive"))
      (node (ref "R22") (pin "2") (pinfunction "2_2") (pintype "passive"))
      (node (ref "R25") (pin "2") (pinfunction "2_2") (pintype "passive"))
      (node (ref "R26") (pin "1") (pinfunction "1_1") (pintype "passive"))
      (node (ref "S1") (pin "1") (pinfunction "1_1") (pintype "passive"))
      (node (ref "SB3") (pin "3") (pinfunction "3_3") (pintype "passive"))
      (node (ref "SB4") (pin "3") (pinfunction "3_3") (pintype "passive"))
      (node (ref "SC1") (pin "2") (pinfunction "-_2") (pintype "passive"))
      (node (ref "U1") (pin "23") (pinfunction "VSS_1_23") (pintype "power_in"))
      (node (ref "U1") (pin "35") (pinfunction "VSS_2_35") (pintype "power_in"))
      (node (ref "U1") (pin "47") (pinfunction "VSS_3_47") (pintype "power_in"))
      (node (ref "U1") (pin "8") (pinfunction "VSSA_8") (pintype "power_in"))
      (node (ref "U2") (pin "4") (pinfunction "GND_4") (pintype "passive"))
      (node (ref "USB1") (pin "5") (pinfunction "GND_5") (pintype "passive"))
    )
    (net (code "26") (name "GND IN") (class "Default")
      (node (ref "*5") (pin "2") (pinfunction "--_2") (pintype "passive"))
      (node (ref "*6") (pin "2") (pinfunction "--_2") (pintype "passive"))
      (node (ref "*7") (pin "2") (pinfunction "--_2") (pintype "passive"))
      (node (ref "C17") (pin "8") (pinfunction "8_8") (pintype "passive"))
      (node (ref "C17") (pin "9") (pinfunction "9_9") (pintype "passive"))
      (node (ref "C18") (pin "1") (pinfunction "1_1") (pintype "passive"))
      (node (ref "C19") (pin "1") (pinfunction "1_1") (pintype "passive"))
      (node (ref "C20") (pin "1") (pinfunction "1_1") (pintype "passive"))
      (node (ref "C21") (pin "2") (pinfunction "2_2") (pintype "passive"))
      (node (ref "L6") (pin "2") (pinfunction "2_2") (pintype "passive"))
    )
    (net (code "27") (name "Net-(*2-Pad1)") (class "Default")
      (node (ref "*2") (pin "1") (pintype "passive"))
      (node (ref "*2") (pin "3") (pintype "passive"))
      (node (ref "D5") (pin "1") (pinfunction "1_1") (pintype "passive"))
      (node (ref "R6") (pin "2") (pinfunction "2_2") (pintype "passive"))
      (node (ref "R7") (pin "2") (pinfunction "2_2") (pintype "passive"))
    )
    (net (code "28") (name "Net-(*5-+)") (class "Default")
      (node (ref "*5") (pin "1") (pinfunction "+_1") (pintype "passive"))
      (node (ref "C18") (pin "2") (pinfunction "2_2") (pintype "passive"))
      (node (ref "L3") (pin "1") (pinfunction "1_1") (pintype "passive"))
    )
    (net (code "29") (name "Net-(*5-~-Pad3)") (class "Default")
      (node (ref "*5") (pin "3") (pinfunction "~_3") (pintype "passive"))
      (node (ref "C17") (pin "15") (pinfunction "15_15") (pintype "passive"))
      (node (ref "C17") (pin "2") (pinfunction "2_2") (pintype "passive"))
    )
    (net (code "30") (name "Net-(*5-~-Pad4)") (class "Default")
      (node (ref "*5") (pin "4") (pinfunction "~_4") (pintype "passive"))
      (node (ref "C17") (pin "1") (pinfunction "1_1") (pintype "passive"))
      (node (ref "C17") (pin "16") (pinfunction "16_16") (pintype "passive"))
    )
    (net (code "31") (name "Net-(*6-+)") (class "Default")
      (node (ref "*6") (pin "1") (pinfunction "+_1") (pintype "passive"))
      (node (ref "C19") (pin "2") (pinfunction "2_2") (pintype "passive"))
      (node (ref "L4") (pin "1") (pinfunction "1_1") (pintype "passive"))
    )
    (net (code "32") (name "Net-(*6-~-Pad3)") (class "Default")
      (node (ref "*6") (pin "3") (pinfunction "~_3") (pintype "passive"))
      (node (ref "C17") (pin "13") (pinfunction "13_13") (pintype "passive"))
      (node (ref "C17") (pin "4") (pinfunction "4_4") (pintype "passive"))
    )
    (net (code "33") (name "Net-(*6-~-Pad4)") (class "Default")
      (node (ref "*6") (pin "4") (pinfunction "~_4") (pintype "passive"))
      (node (ref "C17") (pin "14") (pinfunction "14_14") (pintype "passive"))
      (node (ref "C17") (pin "3") (pinfunction "3_3") (pintype "passive"))
    )
    (net (code "34") (name "Net-(*7-+)") (class "Default")
      (node (ref "*7") (pin "1") (pinfunction "+_1") (pintype "passive"))
      (node (ref "C20") (pin "2") (pinfunction "2_2") (pintype "passive"))
      (node (ref "L5") (pin "1") (pinfunction "1_1") (pintype "passive"))
    )
    (net (code "35") (name "Net-(*7-~-Pad3)") (class "Default")
      (node (ref "*7") (pin "3") (pinfunction "~_3") (pintype "passive"))
      (node (ref "C17") (pin "11") (pinfunction "11_11") (pintype "passive"))
      (node (ref "C17") (pin "6") (pinfunction "6_6") (pintype "passive"))
    )
    (net (code "36") (name "Net-(*7-~-Pad4)") (class "Default")
      (node (ref "*7") (pin "4") (pinfunction "~_4") (pintype "passive"))
      (node (ref "C17") (pin "12") (pinfunction "12_12") (pintype "passive"))
      (node (ref "C17") (pin "5") (pinfunction "5_5") (pintype "passive"))
    )
    (net (code "37") (name "Net-(B1-AAM)") (class "Default")
      (node (ref "B1") (pin "1") (pinfunction "AAM_1") (pintype "passive"))
      (node (ref "R1") (pin "1") (pinfunction "1_1") (pintype "passive"))
      (node (ref "R2") (pin "2") (pinfunction "2_2") (pintype "passive"))
    )
    (net (code "38") (name "Net-(B1-BST)") (class "Default")
      (node (ref "B1") (pin "5") (pinfunction "BST_5") (pintype "passive"))
      (node (ref "R3") (pin "2") (pinfunction "2_2") (pintype "passive"))
    )
    (net (code "39") (name "Net-(B1-EN{slash}SYNC)") (class "Default")
      (node (ref "B1") (pin "6") (pinfunction "EN/SYNC_6") (pintype "passive"))
      (node (ref "R4") (pin "2") (pinfunction "2_2") (pintype "passive"))
    )
    (net (code "40") (name "Net-(B1-FB)") (class "Default")
      (node (ref "B1") (pin "8") (pinfunction "FB_8") (pintype "passive"))
      (node (ref "R9") (pin "1") (pinfunction "1_1") (pintype "passive"))
    )
    (net (code "41") (name "Net-(B1-SW)") (class "Default")
      (node (ref "B1") (pin "3") (pinfunction "SW_3") (pintype "passive"))
      (node (ref "C2") (pin "1") (pinfunction "1_1") (pintype "passive"))
      (node (ref "L1") (pin "1") (pinfunction "1_1") (pintype "passive"))
    )
    (net (code "42") (name "Net-(B1-VCC)") (class "Default")
      (node (ref "B1") (pin "7") (pinfunction "VCC_7") (pintype "passive"))
      (node (ref "C1") (pin "1") (pinfunction "1_1") (pintype "passive"))
      (node (ref "R2") (pin "1") (pinfunction "1_1") (pintype "passive"))
    )
    (net (code "43") (name "Net-(BT1-+3V)") (class "Default")
      (node (ref "BT1") (pin "1") (pinfunction "+3V_1") (pintype "passive"))
      (node (ref "D12") (pin "1") (pinfunction "1_1") (pintype "passive"))
    )
    (net (code "44") (name "Net-(C2-Pad2)") (class "Default")
      (node (ref "C2") (pin "2") (pinfunction "2_2") (pintype "passive"))
      (node (ref "R3") (pin "1") (pinfunction "1_1") (pintype "passive"))
    )
    (net (code "45") (name "Net-(C8-Pad1)") (class "Default")
      (node (ref "C8") (pin "1") (pinfunction "1_1") (pintype "passive"))
      (node (ref "R10") (pin "1") (pinfunction "1_1") (pintype "passive"))
      (node (ref "R8") (pin "2") (pinfunction "2_2") (pintype "passive"))
      (node (ref "R9") (pin "2") (pinfunction "2_2") (pintype "passive"))
    )
    (net (code "46") (name "Net-(C21-Pad1)") (class "Default")
      (node (ref "C21") (pin "1") (pinfunction "1_1") (pintype "passive"))
      (node (ref "D10") (pin "2") (pinfunction "2_2") (pintype "passive"))
      (node (ref "D11") (pin "2") (pinfunction "2_2") (pintype "passive"))
      (node (ref "D8") (pin "2") (pinfunction "2_2") (pintype "passive"))
      (node (ref "D9") (pin "2") (pinfunction "2_2") (pintype "passive"))
      (node (ref "L2") (pin "1") (pinfunction "1_1") (pintype "passive"))
    )
    (net (code "47") (name "Net-(D2-Pad2)") (class "Default")
      (node (ref "D2") (pin "2") (pinfunction "2_2") (pintype "passive"))
      (node (ref "D3") (pin "1") (pinfunction "1_1") (pintype "passive"))
      (node (ref "SB1") (pin "1") (pintype "passive"))
    )
    (net (code "48") (name "Net-(LED1-Pad1)") (class "Default")
      (node (ref "LED1") (pin "1") (pinfunction "1_1") (pintype "passive"))
      (node (ref "R5") (pin "1") (pinfunction "1_1") (pintype "passive"))
    )
    (net (code "49") (name "Net-(LED2-Pad1)") (class "Default")
      (node (ref "LED2") (pin "1") (pinfunction "1_1") (pintype "passive"))
      (node (ref "R23") (pin "1") (pinfunction "1_1") (pintype "passive"))
    )
    (net (code "50") (name "Net-(LED3-Pad2)") (class "Default")
      (node (ref "LED3") (pin "2") (pinfunction "2_2") (pintype "passive"))
      (node (ref "R25") (pin "1") (pinfunction "1_1") (pintype "passive"))
    )
    (net (code "51") (name "Net-(LS1-LEAD_-)") (class "Default")
      (node (ref "*3") (pin "2") (pintype "passive"))
      (node (ref "D6") (pin "1") (pinfunction "1_1") (pintype "passive"))
      (node (ref "LS1") (pin "3") (pinfunction "LEAD_-_3") (pintype "passive"))
    )
    (net (code "52") (name "Net-(M1-ANT)") (class "Default")
      (node (ref "*4") (pin "1") (pinfunction "1_1") (pintype "passive"))
      (node (ref "M1") (pin "6") (pinfunction "ANT_6") (pintype "passive"))
    )
    (net (code "53") (name "Net-(M1-SET)") (class "Default")
      (node (ref "M1") (pin "5") (pinfunction "SET_5") (pintype "passive"))
      (node (ref "SB2") (pin "2") (pinfunction "2_2") (pintype "passive"))
    )
    (net (code "54") (name "Net-(SC1-+)") (class "Default")
      (node (ref "*1") (pin "1") (pintype "passive"))
      (node (ref "*1") (pin "3") (pintype "passive"))
      (node (ref "*2") (pin "2") (pintype "passive"))
      (node (ref "D4") (pin "1") (pinfunction "1_1") (pintype "passive"))
      (node (ref "D5") (pin "2") (pinfunction "2_2") (pintype "passive"))
      (node (ref "SC1") (pin "1") (pinfunction "+_1") (pintype "passive"))
    )
    (net (code "55") (name "Net-(U1A-PA8{slash}USART1_CK{slash}TIM1_CH1{slash}MCO)") (class "Default")
      (node (ref "R24") (pin "1") (pinfunction "1_1") (pintype "passive"))
      (node (ref "U1") (pin "29") (pinfunction "PA8/USART1_CK/TIM1_CH1/MCO_29") (pintype "bidirectional"))
    )
    (net (code "56") (name "Net-(U1A-PA13{slash}JTMS{slash}SWDIO)") (class "Default")
      (node (ref "C22") (pin "3") (pinfunction "3_3") (pintype "passive"))
      (node (ref "U1") (pin "34") (pinfunction "PA13/JTMS/SWDIO_34") (pintype "bidirectional"))
    )
    (net (code "57") (name "Net-(U1A-PA14{slash}JTCK{slash}SWCLK)") (class "Default")
      (node (ref "C22") (pin "4") (pinfunction "4_4") (pintype "passive"))
      (node (ref "U1") (pin "37") (pinfunction "PA14/JTCK/SWCLK_37") (pintype "bidirectional"))
    )
    (net (code "58") (name "Net-(U1A-PB2{slash}BOOT1)") (class "Default")
      (node (ref "SB3") (pin "2") (pinfunction "2_2") (pintype "passive"))
      (node (ref "U1") (pin "20") (pinfunction "PB2/BOOT1_20") (pintype "bidirectional"))
    )
    (net (code "59") (name "Net-(U1A-PB13{slash}SPI2_SCK{slash}USART3_CTS{slash}TIM1_CH1N)") (class "Default")
      (node (ref "LED3") (pin "1") (pinfunction "1_1") (pintype "passive"))
      (node (ref "U1") (pin "26") (pinfunction "PB13/SPI2_SCK/USART3_CTS/TIM1_CH1N_26") (pintype "bidirectional"))
    )
    (net (code "60") (name "Net-(U1A-PB14{slash}SPI2_MISO{slash}USART3_RTS{slash}TIM1_CH2N)") (class "Default")
      (node (ref "LED2") (pin "2") (pinfunction "2_2") (pintype "passive"))
      (node (ref "U1") (pin "27") (pinfunction "PB14/SPI2_MISO/USART3_RTS/TIM1_CH2N_27") (pintype "bidirectional"))
    )
    (net (code "61") (name "Net-(U1A-PC14-OSC32_IN)") (class "Default")
      (node (ref "C23") (pin "1") (pinfunction "1_1") (pintype "passive"))
      (node (ref "U1") (pin "3") (pinfunction "PC14-OSC32_IN_3") (pintype "bidirectional"))
      (node (ref "X1") (pin "2") (pinfunction "2_2") (pintype "passive"))
    )
    (net (code "62") (name "Net-(U1A-PC15-OSC32_OUT)") (class "Default")
      (node (ref "C24") (pin "1") (pinfunction "1_1") (pintype "passive"))
      (node (ref "U1") (pin "4") (pinfunction "PC15-OSC32_OUT_4") (pintype "bidirectional"))
      (node (ref "X1") (pin "1") (pinfunction "1_1") (pintype "passive"))
    )
    (net (code "63") (name "Net-(U1A-PD0-OSC_IN)") (class "Default")
      (node (ref "C25") (pin "1") (pinfunction "1_1") (pintype "passive"))
      (node (ref "R28") (pin "2") (pinfunction "2_2") (pintype "passive"))
      (node (ref "U1") (pin "5") (pinfunction "PD0-OSC_IN_5") (pintype "bidirectional"))
      (node (ref "X2") (pin "2") (pinfunction "2_2") (pintype "passive"))
    )
    (net (code "64") (name "Net-(U1A-PD1-OSC_OUT)") (class "Default")
      (node (ref "C27") (pin "1") (pinfunction "1_1") (pintype "passive"))
      (node (ref "R28") (pin "1") (pinfunction "1_1") (pintype "passive"))
      (node (ref "U1") (pin "6") (pinfunction "PD1-OSC_OUT_6") (pintype "bidirectional"))
      (node (ref "X2") (pin "1") (pinfunction "1_1") (pintype "passive"))
    )
    (net (code "65") (name "Net-(U1B-VBAT)") (class "Default")
      (node (ref "C28") (pin "2") (pinfunction "2_2") (pintype "passive"))
      (node (ref "D12") (pin "2") (pinfunction "2_2") (pintype "passive"))
      (node (ref "D13") (pin "2") (pinfunction "2_2") (pintype "passive"))
      (node (ref "U1") (pin "1") (pinfunction "VBAT_1") (pintype "power_in"))
    )
    (net (code "66") (name "Net-(U1B-VDDA)") (class "Default")
      (node (ref "C30") (pin "1") (pinfunction "1_1") (pintype "passive"))
      (node (ref "C31") (pin "1") (pinfunction "1_1") (pintype "passive"))
      (node (ref "C32") (pin "1") (pinfunction "1_1") (pintype "passive"))
      (node (ref "C33") (pin "1") (pinfunction "1_1") (pintype "passive"))
      (node (ref "C34") (pin "1") (pinfunction "1_1") (pintype "passive"))
      (node (ref "D13") (pin "1") (pinfunction "1_1") (pintype "passive"))
      (node (ref "L7") (pin "1") (pinfunction "1_1") (pintype "passive"))
      (node (ref "U1") (pin "24") (pinfunction "VDD_1_24") (pintype "power_in"))
      (node (ref "U1") (pin "36") (pinfunction "VDD_2_36") (pintype "power_in"))
      (node (ref "U1") (pin "48") (pinfunction "VDD_3_48") (pintype "power_in"))
      (node (ref "U1") (pin "9") (pinfunction "VDDA_9") (pintype "power_in"))
    )
    (net (code "67") (name "Net-(USB1-VCC)") (class "Default")
      (node (ref "D7") (pin "1") (pinfunction "1_1") (pintype "passive"))
      (node (ref "USB1") (pin "1") (pinfunction "VCC_1") (pintype "passive"))
    )
    (net (code "68") (name "VCC IN") (class "Default")
      (node (ref "C17") (pin "10") (pinfunction "10_10") (pintype "passive"))
      (node (ref "C17") (pin "7") (pinfunction "7_7") (pintype "passive"))
      (node (ref "D9") (pin "1") (pinfunction "1_1") (pintype "passive"))
    )
    (net (code "69") (name "V_BUCK") (class "Default")
      (node (ref "*TP1") (pin "1") (pintype "passive"))
      (node (ref "B1") (pin "2") (pinfunction "IN_2") (pintype "passive"))
      (node (ref "C3") (pin "1") (pinfunction "1_1") (pintype "passive"))
      (node (ref "D1") (pin "2") (pinfunction "2_2") (pintype "passive"))
      (node (ref "L2") (pin "2") (pinfunction "2_2") (pintype "passive"))
      (node (ref "R14") (pin "1") (pinfunction "1_1") (pintype "passive"))
      (node (ref "R4") (pin "1") (pinfunction "1_1") (pintype "passive"))
    )
    (net (code "70") (name "unconnected-(MU1-AD0-Pad7)") (class "Default")
      (node (ref "MU1") (pin "7") (pinfunction "AD0_7") (pintype "passive"))
    )
    (net (code "71") (name "unconnected-(MU1-INT-Pad8)") (class "Default")
      (node (ref "MU1") (pin "8") (pinfunction "INT_8") (pintype "passive"))
    )
    (net (code "72") (name "unconnected-(MU1-XCL-Pad6)") (class "Default")
      (node (ref "MU1") (pin "6") (pinfunction "XCL_6") (pintype "passive"))
    )
    (net (code "73") (name "unconnected-(MU1-XDA-Pad5)") (class "Default")
      (node (ref "MU1") (pin "5") (pinfunction "XDA_5") (pintype "passive"))
    )
    (net (code "74") (name "unconnected-(U1A-PA0-WKUP{slash}PA0{slash}WKUP{slash}USART2_CTS{slash}ADC12_IN0{slash}TIM2_CH1_ETR-Pad10)") (class "Default")
      (node (ref "U1") (pin "10") (pinfunction "PA0-WKUP/PA0/WKUP/USART2_CTS/ADC12_IN0/TIM2_CH1_ETR_10") (pintype "bidirectional"))
    )
    (net (code "75") (name "unconnected-(U1A-PA1{slash}USART2_RTS{slash}ADC12_IN1{slash}TIM2_CH2-Pad11)") (class "Default")
      (node (ref "U1") (pin "11") (pinfunction "PA1/USART2_RTS/ADC12_IN1/TIM2_CH2_11") (pintype "bidirectional"))
    )
    (net (code "76") (name "unconnected-(U1A-PA2{slash}USART2_TX{slash}ADC12_IN2{slash}TIM2_CH3-Pad12)") (class "Default")
      (node (ref "U1") (pin "12") (pinfunction "PA2/USART2_TX/ADC12_IN2/TIM2_CH3_12") (pintype "bidirectional"))
    )
    (net (code "77") (name "unconnected-(U1A-PA15{slash}JTDI{slash}TIM2_CH1_ETR{slash}SPI1_NSS-Pad38)") (class "Default")
      (node (ref "U1") (pin "38") (pinfunction "PA15/JTDI/TIM2_CH1_ETR/SPI1_NSS_38") (pintype "bidirectional"))
    )
    (net (code "78") (name "unconnected-(U1A-PB0{slash}ADC12_IN8{slash}TIM3_CH3{slash}TIM1_CH2N-Pad18)") (class "Default")
      (node (ref "U1") (pin "18") (pinfunction "PB0/ADC12_IN8/TIM3_CH3/TIM1_CH2N_18") (pintype "bidirectional"))
    )
    (net (code "79") (name "unconnected-(U1A-PB8{slash}TIM4_CH3{slash}I2C1_SCL{slash}CANRX-Pad45)") (class "Default")
      (node (ref "U1") (pin "45") (pinfunction "PB8/TIM4_CH3/I2C1_SCL/CANRX_45") (pintype "bidirectional"))
    )
    (net (code "80") (name "unconnected-(U1A-PB9{slash}TIM4_CH4{slash}I2C1_SDA{slash}CANTX-Pad46)") (class "Default")
      (node (ref "U1") (pin "46") (pinfunction "PB9/TIM4_CH4/I2C1_SDA/CANTX_46") (pintype "bidirectional"))
    )
    (net (code "81") (name "unconnected-(U1A-PB15{slash}SPI2_MOSI{slash}TIM1_CH3N-Pad28)") (class "Default")
      (node (ref "U1") (pin "28") (pinfunction "PB15/SPI2_MOSI/TIM1_CH3N_28") (pintype "bidirectional"))
    )
    (net (code "82") (name "unconnected-(U1A-PC13-TAMPER-RTC-Pad2)") (class "Default")
      (node (ref "U1") (pin "2") (pinfunction "PC13-TAMPER-RTC_2") (pintype "bidirectional"))
    )
  )
)
